# design1.net
KiCad netlist of a schematic drawn in EAGLE
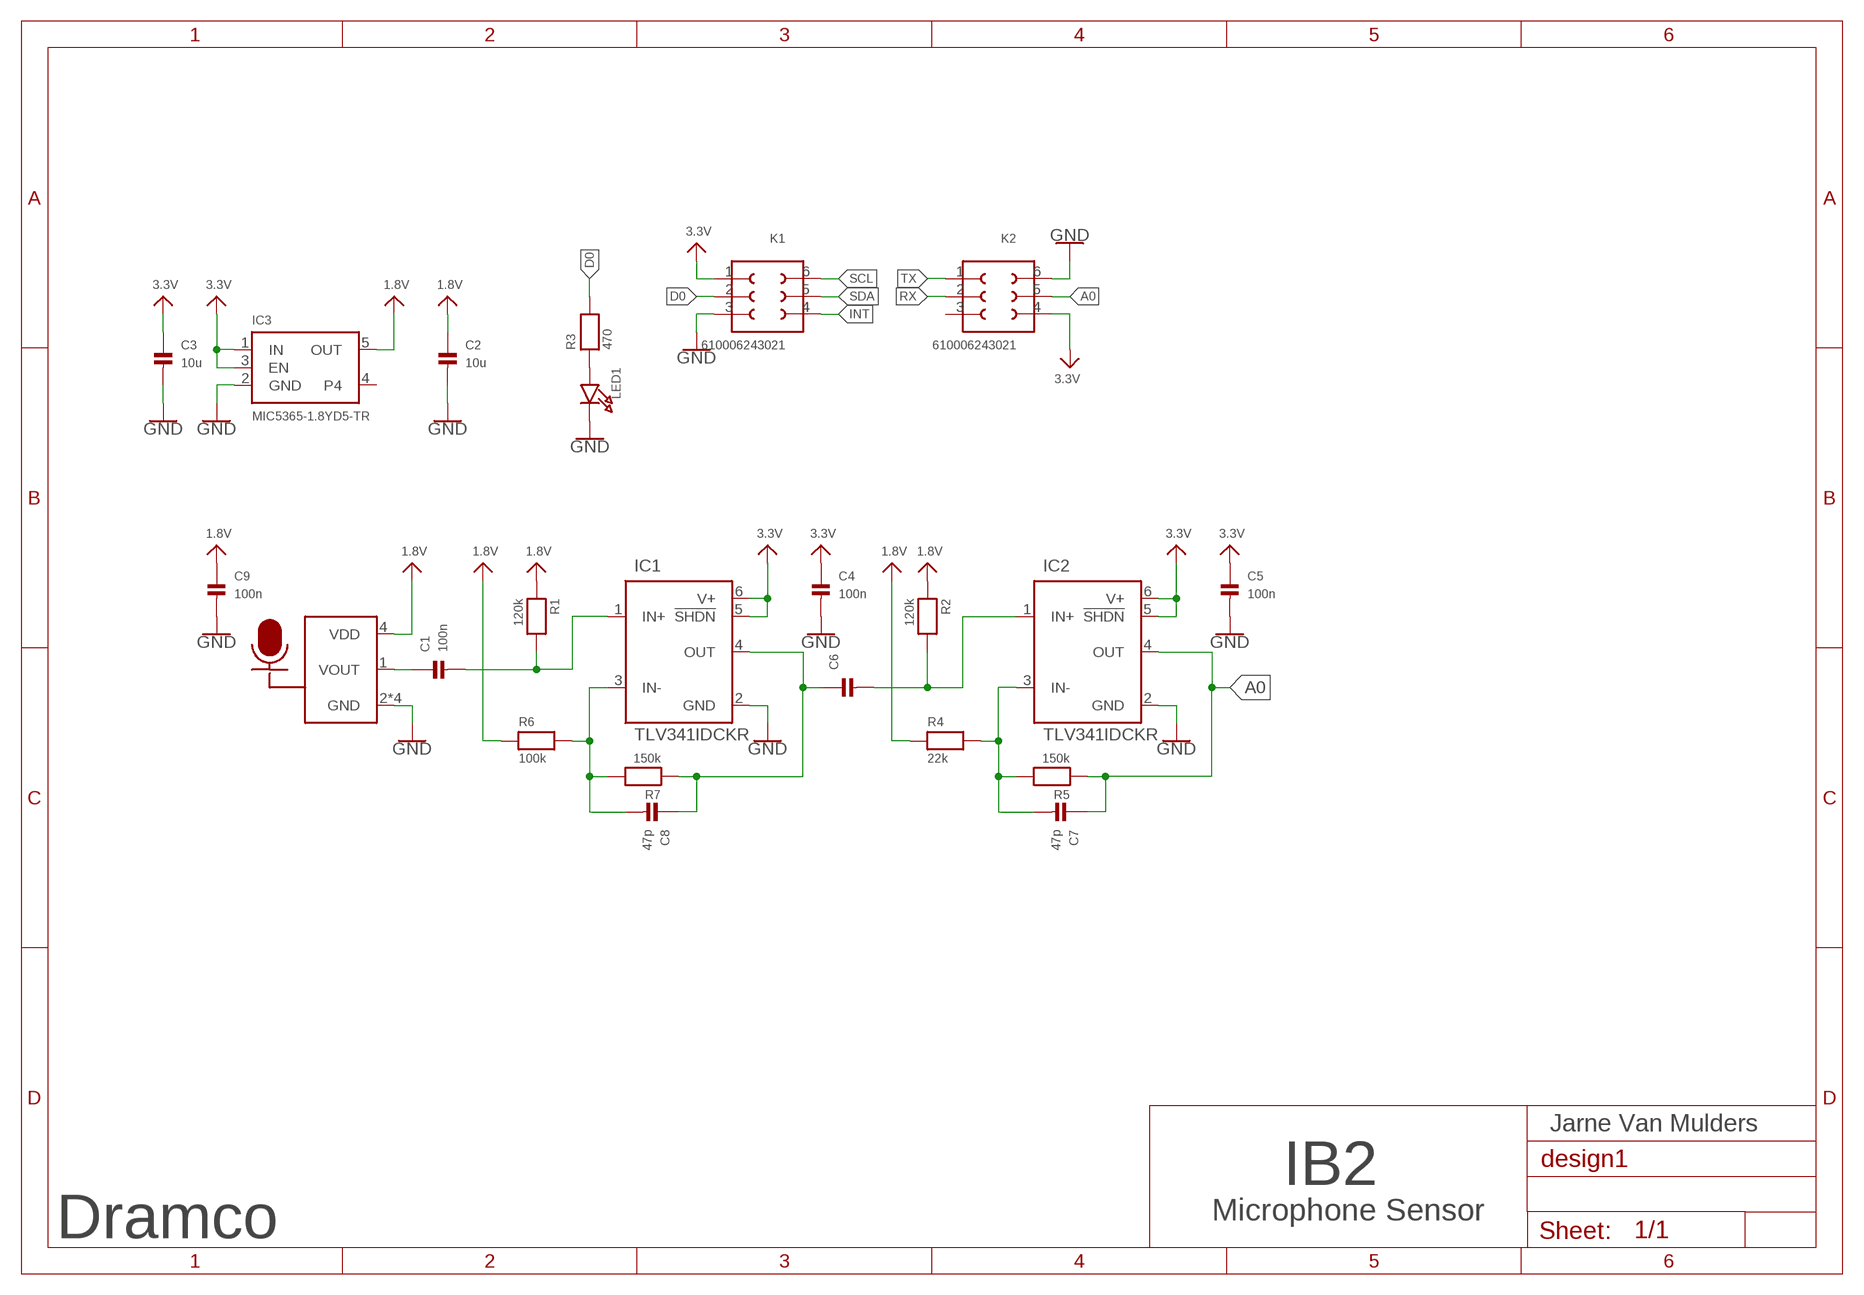
[diagram p0: schematic, sheet 1]

(export (version "E")
  (design (tool "Eeschema 10.0.6"))
  (components
    (comp (ref "C1")
      (value "100n")
      (footprint "eagle-import:0603-MINI")
      (libsource (lib "eagle-import") (part "CAP_CERAMIC0603MINI"))
    )
    (comp (ref "C2")
      (value "10u")
      (footprint "eagle-import:0603-MINI")
      (libsource (lib "eagle-import") (part "CAP_CERAMIC0603MINI"))
    )
    (comp (ref "C3")
      (value "10u")
      (footprint "eagle-import:0603-MINI")
      (libsource (lib "eagle-import") (part "CAP_CERAMIC0603MINI"))
    )
    (comp (ref "C4")
      (value "100n")
      (footprint "eagle-import:0603-MINI")
      (libsource (lib "eagle-import") (part "CAP_CERAMIC0603MINI"))
    )
    (comp (ref "C5")
      (value "100n")
      (footprint "eagle-import:0603-MINI")
      (libsource (lib "eagle-import") (part "CAP_CERAMIC0603MINI"))
    )
    (comp (ref "C6")
      (value "CAP_CERAMIC0603MINI")
      (footprint "eagle-import:0603-MINI")
      (libsource (lib "eagle-import") (part "CAP_CERAMIC0603MINI"))
    )
    (comp (ref "C7")
      (value "47p")
      (footprint "eagle-import:0603-MINI")
      (libsource (lib "eagle-import") (part "CAP_CERAMIC0603MINI"))
    )
    (comp (ref "C8")
      (value "47p")
      (footprint "eagle-import:0603-MINI")
      (libsource (lib "eagle-import") (part "CAP_CERAMIC0603MINI"))
    )
    (comp (ref "C9")
      (value "100n")
      (footprint "eagle-import:0603-MINI")
      (libsource (lib "eagle-import") (part "CAP_CERAMIC0603MINI"))
    )
    (comp (ref "IC1")
      (value "TLV341IDCKR")
      (footprint "eagle-import:SOT65P210X110-6N")
      (libsource (lib "eagle-import") (part "TLV341IDCKR"))
    )
    (comp (ref "IC2")
      (value "TLV341IDCKR")
      (footprint "eagle-import:SOT65P210X110-6N")
      (libsource (lib "eagle-import") (part "TLV341IDCKR"))
    )
    (comp (ref "IC3")
      (value "MIC5365-1.8YD5-TR")
      (footprint "eagle-import:SOT23-5")
      (libsource (lib "eagle-import") (part "VREG_SOT23-5"))
    )
    (comp (ref "IC4")
      (value "VM1000")
      (footprint "eagle-import:VM1000")
      (libsource (lib "eagle-import") (part "VM1000"))
    )
    (comp (ref "K1")
      (value "610006243021")
      (footprint "eagle-import:610006243021")
      (libsource (lib "eagle-import") (part "610006243021"))
    )
    (comp (ref "K2")
      (value "610006243021")
      (footprint "eagle-import:610006243021")
      (libsource (lib "eagle-import") (part "610006243021"))
    )
    (comp (ref "LED1")
      (value "LED0805")
      (footprint "eagle-import:CHIPLED_0805")
      (libsource (lib "eagle-import") (part "LED0805"))
    )
    (comp (ref "R1")
      (value "120k")
      (footprint "eagle-import:0603-MINI")
      (libsource (lib "eagle-import") (part "RESISTOR0603MINI"))
    )
    (comp (ref "R2")
      (value "120k")
      (footprint "eagle-import:0603-MINI")
      (libsource (lib "eagle-import") (part "RESISTOR0603MINI"))
    )
    (comp (ref "R3")
      (value "470")
      (footprint "eagle-import:0603-MINI")
      (libsource (lib "eagle-import") (part "RESISTOR0603MINI"))
    )
    (comp (ref "R4")
      (value "22k")
      (footprint "eagle-import:0603-MINI")
      (libsource (lib "eagle-import") (part "RESISTOR0603MINI"))
    )
    (comp (ref "R5")
      (value "150k")
      (footprint "eagle-import:0603-MINI")
      (libsource (lib "eagle-import") (part "RESISTOR0603MINI"))
    )
    (comp (ref "R6")
      (value "100k")
      (footprint "eagle-import:0603-MINI")
      (libsource (lib "eagle-import") (part "RESISTOR0603MINI"))
    )
    (comp (ref "R7")
      (value "150k")
      (footprint "eagle-import:0603-MINI")
      (libsource (lib "eagle-import") (part "RESISTOR0603MINI"))
    )
  )
  (nets
    (net (code "1") (name "1.8V") (class "Default")
      (node (ref "C2") (pin "1") (pinfunction "P$1_1") (pintype "passive"))
      (node (ref "C9") (pin "1") (pinfunction "P$1_1") (pintype "passive"))
      (node (ref "IC3") (pin "5") (pinfunction "OUT_5") (pintype "bidirectional"))
      (node (ref "IC4") (pin "4") (pinfunction "VDD_4") (pintype "bidirectional"))
      (node (ref "R1") (pin "1") (pinfunction "1_1") (pintype "passive"))
      (node (ref "R2") (pin "1") (pinfunction "1_1") (pintype "passive"))
      (node (ref "R4") (pin "1") (pinfunction "1_1") (pintype "passive"))
      (node (ref "R6") (pin "1") (pinfunction "1_1") (pintype "passive"))
    )
    (net (code "2") (name "3.3V") (class "Default")
      (node (ref "C3") (pin "1") (pinfunction "P$1_1") (pintype "passive"))
      (node (ref "C4") (pin "1") (pinfunction "P$1_1") (pintype "passive"))
      (node (ref "C5") (pin "1") (pinfunction "P$1_1") (pintype "passive"))
      (node (ref "IC1") (pin "5") (pinfunction "~{SHDN}_5") (pintype "bidirectional"))
      (node (ref "IC1") (pin "6") (pinfunction "V+_6") (pintype "bidirectional"))
      (node (ref "IC2") (pin "5") (pinfunction "~{SHDN}_5") (pintype "bidirectional"))
      (node (ref "IC2") (pin "6") (pinfunction "V+_6") (pintype "bidirectional"))
      (node (ref "IC3") (pin "1") (pinfunction "IN_1") (pintype "bidirectional"))
      (node (ref "IC3") (pin "3") (pinfunction "EN_3") (pintype "bidirectional"))
      (node (ref "K1") (pin "1") (pinfunction "1_1") (pintype "passive"))
      (node (ref "K2") (pin "4") (pinfunction "4_4") (pintype "passive"))
    )
    (net (code "3") (name "A0") (class "Default")
      (node (ref "C7") (pin "1") (pinfunction "P$1_1") (pintype "passive"))
      (node (ref "IC2") (pin "4") (pinfunction "OUT_4") (pintype "bidirectional"))
      (node (ref "K2") (pin "5") (pinfunction "5_5") (pintype "passive"))
      (node (ref "R5") (pin "1") (pinfunction "1_1") (pintype "passive"))
    )
    (net (code "4") (name "D0") (class "Default")
      (node (ref "K1") (pin "2") (pinfunction "2_2") (pintype "passive"))
      (node (ref "R3") (pin "2") (pinfunction "2_2") (pintype "passive"))
    )
    (net (code "5") (name "GND") (class "Default")
      (node (ref "C2") (pin "2") (pinfunction "P$2_2") (pintype "passive"))
      (node (ref "C3") (pin "2") (pinfunction "P$2_2") (pintype "passive"))
      (node (ref "C4") (pin "2") (pinfunction "P$2_2") (pintype "passive"))
      (node (ref "C5") (pin "2") (pinfunction "P$2_2") (pintype "passive"))
      (node (ref "C9") (pin "2") (pinfunction "P$2_2") (pintype "passive"))
      (node (ref "IC1") (pin "2") (pinfunction "GND_2") (pintype "bidirectional"))
      (node (ref "IC2") (pin "2") (pinfunction "GND_2") (pintype "bidirectional"))
      (node (ref "IC3") (pin "2") (pinfunction "GND_2") (pintype "bidirectional"))
      (node (ref "IC4") (pin "2") (pinfunction "GND_2") (pintype "bidirectional"))
      (node (ref "IC4") (pin "3") (pinfunction "GND_3") (pintype "bidirectional"))
      (node (ref "IC4") (pin "5") (pinfunction "GND_5") (pintype "bidirectional"))
      (node (ref "IC4") (pin "6") (pinfunction "GND_6") (pintype "bidirectional"))
      (node (ref "K1") (pin "3") (pinfunction "3_3") (pintype "passive"))
      (node (ref "K2") (pin "6") (pinfunction "6_6") (pintype "passive"))
      (node (ref "LED1") (pin "C") (pinfunction "C_C") (pintype "passive"))
    )
    (net (code "6") (name "INT") (class "Default")
      (node (ref "K1") (pin "4") (pinfunction "4_4") (pintype "passive"))
    )
    (net (code "7") (name "Net-(C1-P$1)") (class "Default")
      (node (ref "C1") (pin "1") (pinfunction "P$1_1") (pintype "passive"))
      (node (ref "IC4") (pin "1") (pinfunction "VOUT_1") (pintype "bidirectional"))
    )
    (net (code "8") (name "Net-(C1-P$2)") (class "Default")
      (node (ref "C1") (pin "2") (pinfunction "P$2_2") (pintype "passive"))
      (node (ref "IC1") (pin "1") (pinfunction "IN+_1") (pintype "bidirectional"))
      (node (ref "R1") (pin "2") (pinfunction "2_2") (pintype "passive"))
    )
    (net (code "9") (name "Net-(C6-P$1)") (class "Default")
      (node (ref "C6") (pin "1") (pinfunction "P$1_1") (pintype "passive"))
      (node (ref "C8") (pin "1") (pinfunction "P$1_1") (pintype "passive"))
      (node (ref "IC1") (pin "4") (pinfunction "OUT_4") (pintype "bidirectional"))
      (node (ref "R7") (pin "1") (pinfunction "1_1") (pintype "passive"))
    )
    (net (code "10") (name "Net-(C6-P$2)") (class "Default")
      (node (ref "C6") (pin "2") (pinfunction "P$2_2") (pintype "passive"))
      (node (ref "IC2") (pin "1") (pinfunction "IN+_1") (pintype "bidirectional"))
      (node (ref "R2") (pin "2") (pinfunction "2_2") (pintype "passive"))
    )
    (net (code "11") (name "Net-(C7-P$2)") (class "Default")
      (node (ref "C7") (pin "2") (pinfunction "P$2_2") (pintype "passive"))
      (node (ref "IC2") (pin "3") (pinfunction "IN-_3") (pintype "bidirectional"))
      (node (ref "R4") (pin "2") (pinfunction "2_2") (pintype "passive"))
      (node (ref "R5") (pin "2") (pinfunction "2_2") (pintype "passive"))
    )
    (net (code "12") (name "Net-(C8-P$2)") (class "Default")
      (node (ref "C8") (pin "2") (pinfunction "P$2_2") (pintype "passive"))
      (node (ref "IC1") (pin "3") (pinfunction "IN-_3") (pintype "bidirectional"))
      (node (ref "R6") (pin "2") (pinfunction "2_2") (pintype "passive"))
      (node (ref "R7") (pin "2") (pinfunction "2_2") (pintype "passive"))
    )
    (net (code "13") (name "Net-(LED1-PadA)") (class "Default")
      (node (ref "LED1") (pin "A") (pinfunction "A_A") (pintype "passive"))
      (node (ref "R3") (pin "1") (pinfunction "1_1") (pintype "passive"))
    )
    (net (code "14") (name "RX") (class "Default")
      (node (ref "K2") (pin "2") (pinfunction "2_2") (pintype "passive"))
    )
    (net (code "15") (name "SCL") (class "Default")
      (node (ref "K1") (pin "6") (pinfunction "6_6") (pintype "passive"))
    )
    (net (code "16") (name "SDA") (class "Default")
      (node (ref "K1") (pin "5") (pinfunction "5_5") (pintype "passive"))
    )
    (net (code "17") (name "TX") (class "Default")
      (node (ref "K2") (pin "1") (pinfunction "1_1") (pintype "passive"))
    )
    (net (code "18") (name "unconnected-(IC3-P4-Pad4)") (class "Default")
      (node (ref "IC3") (pin "4") (pinfunction "P4_4") (pintype "bidirectional"))
    )
    (net (code "19") (name "unconnected-(K2-Pad3)") (class "Default")
      (node (ref "K2") (pin "3") (pinfunction "3_3") (pintype "passive"))
    )
  )
)
